# Esquematico_Luximetro.net
KiCad netlist of a schematic drawn in Altium Designer
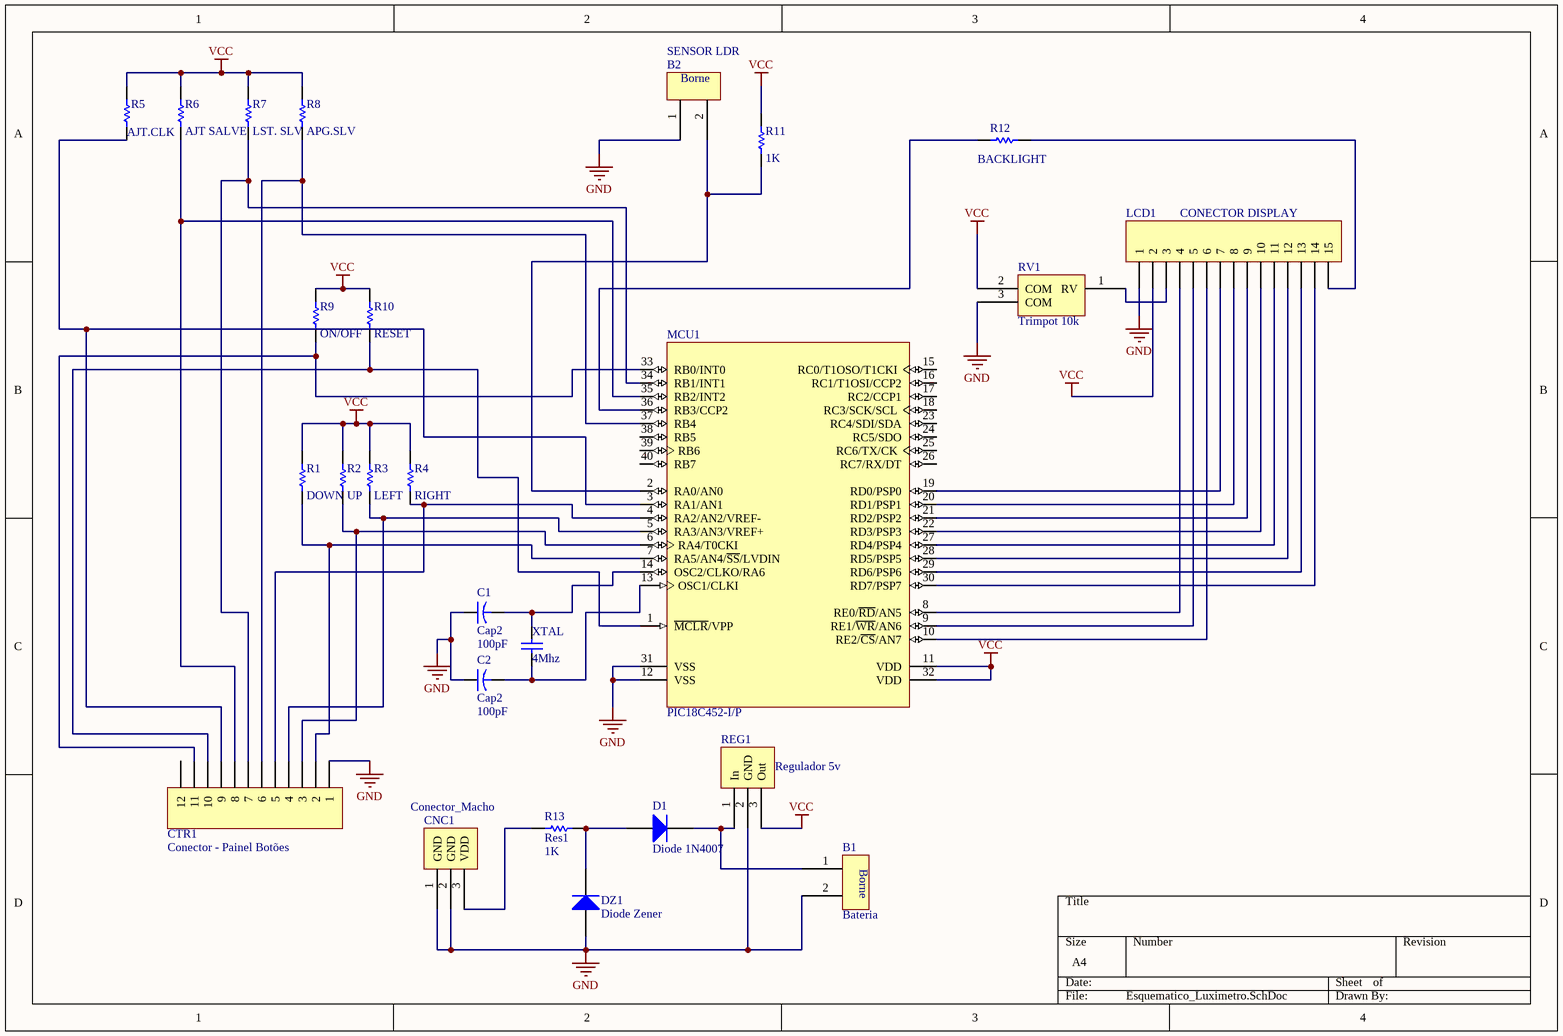
[diagram p0: Esquematico_Luximetro.SchDoc]

(export (version "E")
  (design (tool "Eeschema 10.0.6"))
  (components
    (comp (ref "B1") (value "Bateria") (footprint "PCB_BORNE") (libsource (lib "") (part "Borne_1")))
    (comp (ref "B2")
      (value "SENSOR LDR")
      (footprint "PCB_BORNE")
      (libsource (lib "Minha_Biblioteca") (part "Borne"))
    )
    (comp (ref "C1")
      (value "Cap2")
      (footprint "CAPR5-4X5")
      (description "Capacitor")
      (fields (field (name "ALTIUM_VALUE") "100pF") (field (name "PUBLISHER") "Altium Limited"))
      (libsource (lib "Miscellaneous Devices") (part "Cap2"))
    )
    (comp (ref "C2")
      (value "Cap2")
      (footprint "CAPR5-4X5")
      (description "Capacitor")
      (fields (field (name "ALTIUM_VALUE") "100pF") (field (name "PUBLISHER") "Altium Limited"))
      (libsource (lib "Miscellaneous Devices") (part "Cap2"))
    )
    (comp (ref "CNC1")
      (value "Conector_Macho")
      (footprint "PCB_Conector")
      (libsource (lib "Minha_Biblioteca") (part "Conector"))
    )
    (comp (ref "CTR1")
      (value "Conector - Painel Botões")
      (footprint "HDR1X12")
      (description "Header, 12-Pin")
      (fields (field (name "PUBLISHER") "Altium Limited"))
      (libsource (lib "Miscellaneous Connectors") (part "Header 12"))
    )
    (comp (ref "D1")
      (value "Diode 1N4007")
      (footprint "DO-41")
      (description "1 Amp General Purpose Rectifier")
      (fields (field (name "PUBLISHER") "Altium Limited"))
      (libsource (lib "Miscellaneous Devices") (part "Diode 1N4007"))
    )
    (comp (ref "DZ1")
      (value "Diode Zener")
      (footprint "DO-41")
      (description "1 Amp General Purpose Rectifier")
      (fields (field (name "PUBLISHER") "Altium Limited"))
      (libsource (lib "Miscellaneous Devices") (part "Diode 1N4007"))
    )
    (comp (ref "LCD1")
      (value "CONECTOR DISPLAY")
      (footprint "HDR1X15")
      (description "Header, 15-Pin")
      (fields (field (name "PUBLISHER") "Altium Limited"))
      (libsource (lib "Miscellaneous Connectors") (part "Header 15"))
    )
    (comp (ref "MCU1")
      (value "PIC18C452-I/P")
      (footprint "PDIP600-40")
      (fields (field (name "PUBLISHER") "Altium Limited"))
      (libsource (lib "Microchip Microcontroller 8-Bit PIC18") (part "PIC18C452-I/P"))
    )
    (comp (ref "R1")
      (value "DOWN")
      (footprint "AXIAL-0.3")
      (description "Resistor")
      (fields (field (name "Comment") "Res2") (field (name "PUBLISHER") "Altium Limited"))
      (libsource (lib "Miscellaneous Devices") (part "Res1"))
    )
    (comp (ref "R2")
      (value "UP")
      (footprint "AXIAL-0.3")
      (description "Resistor")
      (fields (field (name "Comment") "Res3") (field (name "PUBLISHER") "Altium Limited"))
      (libsource (lib "Miscellaneous Devices") (part "Res1"))
    )
    (comp (ref "R3")
      (value "LEFT")
      (footprint "AXIAL-0.3")
      (description "Resistor")
      (fields (field (name "Comment") "Res4") (field (name "PUBLISHER") "Altium Limited"))
      (libsource (lib "Miscellaneous Devices") (part "Res1"))
    )
    (comp (ref "R4")
      (value "RIGHT")
      (footprint "AXIAL-0.3")
      (description "Resistor")
      (fields (field (name "Comment") "Res5") (field (name "PUBLISHER") "Altium Limited"))
      (libsource (lib "Miscellaneous Devices") (part "Res1"))
    )
    (comp (ref "R5")
      (value "AJT.CLK")
      (footprint "AXIAL-0.3")
      (description "Resistor")
      (fields (field (name "Comment") "Res1") (field (name "PUBLISHER") "Altium Limited"))
      (libsource (lib "Miscellaneous Devices") (part "Res1"))
    )
    (comp (ref "R6")
      (value "AJT SALVE")
      (footprint "AXIAL-0.3")
      (description "Resistor")
      (fields (field (name "Comment") "Res1") (field (name "PUBLISHER") "Altium Limited"))
      (libsource (lib "Miscellaneous Devices") (part "Res1"))
    )
    (comp (ref "R7")
      (value "LST. SLV")
      (footprint "AXIAL-0.3")
      (description "Resistor")
      (fields (field (name "Comment") "Res1") (field (name "PUBLISHER") "Altium Limited"))
      (libsource (lib "Miscellaneous Devices") (part "Res1"))
    )
    (comp (ref "R8")
      (value "APG.SLV")
      (footprint "AXIAL-0.3")
      (description "Resistor")
      (fields (field (name "Comment") "Res1") (field (name "PUBLISHER") "Altium Limited"))
      (libsource (lib "Miscellaneous Devices") (part "Res1"))
    )
    (comp (ref "R9")
      (value "ON/OFF")
      (footprint "AXIAL-0.3")
      (description "Resistor")
      (fields (field (name "Comment") "Res1") (field (name "PUBLISHER") "Altium Limited"))
      (libsource (lib "Miscellaneous Devices") (part "Res1"))
    )
    (comp (ref "R10")
      (value "RESET")
      (footprint "AXIAL-0.3")
      (description "Resistor")
      (fields (field (name "Comment") "Res1") (field (name "PUBLISHER") "Altium Limited"))
      (libsource (lib "Miscellaneous Devices") (part "Res1"))
    )
    (comp (ref "R11")
      (value "1K")
      (footprint "AXIAL-0.3")
      (description "Resistor")
      (fields (field (name "Comment") "Res5") (field (name "PUBLISHER") "Altium Limited"))
      (libsource (lib "Miscellaneous Devices") (part "Res1"))
    )
    (comp (ref "R12")
      (value "BACKLIGHT")
      (footprint "AXIAL-0.3")
      (description "Resistor")
      (fields (field (name "PUBLISHER") "Altium Limited"))
      (libsource (lib "Miscellaneous Devices") (part "Res1"))
    )
    (comp (ref "R13")
      (value "Res1")
      (footprint "AXIAL-0.3")
      (description "Resistor")
      (fields (field (name "ALTIUM_VALUE") "1K") (field (name "PUBLISHER") "Altium Limited"))
      (libsource (lib "Miscellaneous Devices") (part "Res1"))
    )
    (comp (ref "REG1")
      (value "Regulador 5v")
      (footprint "PCB_CI7805")
      (libsource (lib "Minha_Biblioteca") (part "Regulador"))
    )
    (comp (ref "RV1")
      (value "Trimpot 10k")
      (footprint "PCB_TRIMPOT")
      (libsource (lib "Minha_Biblioteca") (part "Trimpot"))
    )
    (comp (ref "XTAL")
      (value "4Mhz")
      (footprint "RAD-0.3")
      (description "Capacitor")
      (fields (field (name "Comment") "Cap") (field (name "PUBLISHER") "Altium Limited"))
      (libsource (lib "Miscellaneous Devices") (part "Cap"))
    )
  )
  (nets
    (net (code "1") (name "GND") (class "Default")
      (node (ref "B1") (pin "2") (pintype "passive"))
      (node (ref "B2") (pin "1") (pintype "passive"))
      (node (ref "C1") (pin "1") (pinfunction "1_1") (pintype "passive"))
      (node (ref "C2") (pin "1") (pinfunction "1_1") (pintype "passive"))
      (node (ref "CNC1") (pin "1") (pinfunction "GND_1") (pintype "passive"))
      (node (ref "CNC1") (pin "2") (pinfunction "GND_2") (pintype "passive"))
      (node (ref "CTR1") (pin "1") (pinfunction "1_1") (pintype "passive"))
      (node (ref "DZ1") (pin "1") (pinfunction "A_1") (pintype "passive"))
      (node (ref "LCD1") (pin "1") (pinfunction "1_1") (pintype "passive"))
      (node (ref "MCU1") (pin "12") (pinfunction "VSS_12") (pintype "power_in"))
      (node (ref "MCU1") (pin "31") (pinfunction "VSS_31") (pintype "power_in"))
      (node (ref "REG1") (pin "2") (pinfunction "GND_2") (pintype "passive"))
      (node (ref "RV1") (pin "3") (pinfunction "COM_3") (pintype "passive"))
    )
    (net (code "2") (name "Net-(CNC1-VDD)") (class "Default")
      (node (ref "CNC1") (pin "3") (pinfunction "VDD_3") (pintype "passive"))
      (node (ref "R13") (pin "1") (pinfunction "1_1") (pintype "passive"))
    )
    (net (code "3") (name "Net-(D1-A)") (class "Default")
      (node (ref "D1") (pin "1") (pinfunction "A_1") (pintype "passive"))
      (node (ref "DZ1") (pin "2") (pinfunction "K_2") (pintype "passive"))
      (node (ref "R13") (pin "2") (pinfunction "2_2") (pintype "passive"))
    )
    (net (code "4") (name "Net-(D1-K)") (class "Default")
      (node (ref "B1") (pin "1") (pintype "passive"))
      (node (ref "D1") (pin "2") (pinfunction "K_2") (pintype "passive"))
      (node (ref "REG1") (pin "1") (pinfunction "In_1") (pintype "passive"))
    )
    (net (code "5") (name "Net-(LCD1-Pad15)") (class "Default")
      (node (ref "LCD1") (pin "15") (pinfunction "15_15") (pintype "passive"))
      (node (ref "R12") (pin "2") (pinfunction "2_2") (pintype "passive"))
    )
    (net (code "6") (name "Net-(MCU1-OSC1{slash}CLKI)") (class "Default")
      (node (ref "C2") (pin "2") (pinfunction "2_2") (pintype "passive"))
      (node (ref "MCU1") (pin "13") (pinfunction "OSC1/CLKI_13") (pintype "input"))
      (node (ref "XTAL") (pin "1") (pinfunction "1_1") (pintype "passive"))
    )
    (net (code "7") (name "Net-(MCU1-OSC2{slash}CLKO{slash}RA6)") (class "Default")
      (node (ref "C1") (pin "2") (pinfunction "2_2") (pintype "passive"))
      (node (ref "MCU1") (pin "14") (pinfunction "OSC2/CLKO/RA6_14") (pintype "bidirectional"))
      (node (ref "XTAL") (pin "2") (pinfunction "2_2") (pintype "passive"))
    )
    (net (code "8") (name "Net-(MCU1-RA0{slash}AN0)") (class "Default")
      (node (ref "B2") (pin "2") (pintype "passive"))
      (node (ref "MCU1") (pin "2") (pinfunction "RA0/AN0_2") (pintype "bidirectional"))
      (node (ref "R11") (pin "2") (pinfunction "2_2") (pintype "passive"))
    )
    (net (code "9") (name "Net-(MCU1-RA1{slash}AN1)") (class "Default")
      (node (ref "CTR1") (pin "9") (pinfunction "9_9") (pintype "passive"))
      (node (ref "MCU1") (pin "3") (pinfunction "RA1/AN1_3") (pintype "bidirectional"))
      (node (ref "R5") (pin "1") (pinfunction "1_1") (pintype "passive"))
    )
    (net (code "10") (name "Net-(MCU1-RA2{slash}AN2{slash}VREF-)") (class "Default")
      (node (ref "CTR1") (pin "5") (pinfunction "5_5") (pintype "passive"))
      (node (ref "MCU1") (pin "4") (pinfunction "RA2/AN2/VREF-_4") (pintype "bidirectional"))
      (node (ref "R4") (pin "2") (pinfunction "2_2") (pintype "passive"))
    )
    (net (code "11") (name "Net-(MCU1-RA3{slash}AN3{slash}VREF+)") (class "Default")
      (node (ref "CTR1") (pin "4") (pinfunction "4_4") (pintype "passive"))
      (node (ref "MCU1") (pin "5") (pinfunction "RA3/AN3/VREF+_5") (pintype "bidirectional"))
      (node (ref "R3") (pin "2") (pinfunction "2_2") (pintype "passive"))
    )
    (net (code "12") (name "Net-(MCU1-RA4{slash}T0CKI)") (class "Default")
      (node (ref "CTR1") (pin "3") (pinfunction "3_3") (pintype "passive"))
      (node (ref "MCU1") (pin "6") (pinfunction "RA4/T0CKI_6") (pintype "bidirectional"))
      (node (ref "R2") (pin "2") (pinfunction "2_2") (pintype "passive"))
    )
    (net (code "13") (name "Net-(MCU1-RA5{slash}AN4{slash}~{SS}{slash}LVDIN)") (class "Default")
      (node (ref "CTR1") (pin "2") (pinfunction "2_2") (pintype "passive"))
      (node (ref "MCU1") (pin "7") (pinfunction "RA5/AN4/~{SS}/LVDIN_7") (pintype "bidirectional"))
      (node (ref "R1") (pin "2") (pinfunction "2_2") (pintype "passive"))
    )
    (net (code "14") (name "Net-(MCU1-RB0{slash}INT0)") (class "Default")
      (node (ref "CTR1") (pin "11") (pinfunction "11_11") (pintype "passive"))
      (node (ref "MCU1") (pin "33") (pinfunction "RB0/INT0_33") (pintype "bidirectional"))
      (node (ref "R9") (pin "2") (pinfunction "2_2") (pintype "passive"))
    )
    (net (code "15") (name "Net-(MCU1-RB1{slash}INT1)") (class "Default")
      (node (ref "CTR1") (pin "7") (pinfunction "7_7") (pintype "passive"))
      (node (ref "MCU1") (pin "34") (pinfunction "RB1/INT1_34") (pintype "bidirectional"))
      (node (ref "R7") (pin "1") (pinfunction "1_1") (pintype "passive"))
    )
    (net (code "16") (name "Net-(MCU1-RB2{slash}INT2)") (class "Default")
      (node (ref "CTR1") (pin "8") (pinfunction "8_8") (pintype "passive"))
      (node (ref "MCU1") (pin "35") (pinfunction "RB2/INT2_35") (pintype "bidirectional"))
      (node (ref "R6") (pin "1") (pinfunction "1_1") (pintype "passive"))
    )
    (net (code "17") (name "Net-(MCU1-RB3{slash}CCP2)") (class "Default")
      (node (ref "MCU1") (pin "36") (pinfunction "RB3/CCP2_36") (pintype "bidirectional"))
      (node (ref "R12") (pin "1") (pinfunction "1_1") (pintype "passive"))
    )
    (net (code "18") (name "Net-(MCU1-RB4)") (class "Default")
      (node (ref "CTR1") (pin "6") (pinfunction "6_6") (pintype "passive"))
      (node (ref "MCU1") (pin "37") (pinfunction "RB4_37") (pintype "bidirectional"))
      (node (ref "R8") (pin "1") (pinfunction "1_1") (pintype "passive"))
    )
    (net (code "19") (name "Net-(MCU1-RD0{slash}PSP0)") (class "Default")
      (node (ref "LCD1") (pin "7") (pinfunction "7_7") (pintype "passive"))
      (node (ref "MCU1") (pin "19") (pinfunction "RD0/PSP0_19") (pintype "bidirectional"))
    )
    (net (code "20") (name "Net-(MCU1-RD1{slash}PSP1)") (class "Default")
      (node (ref "LCD1") (pin "8") (pinfunction "8_8") (pintype "passive"))
      (node (ref "MCU1") (pin "20") (pinfunction "RD1/PSP1_20") (pintype "bidirectional"))
    )
    (net (code "21") (name "Net-(MCU1-RD2{slash}PSP2)") (class "Default")
      (node (ref "LCD1") (pin "9") (pinfunction "9_9") (pintype "passive"))
      (node (ref "MCU1") (pin "21") (pinfunction "RD2/PSP2_21") (pintype "bidirectional"))
    )
    (net (code "22") (name "Net-(MCU1-RD3{slash}PSP3)") (class "Default")
      (node (ref "LCD1") (pin "10") (pinfunction "10_10") (pintype "passive"))
      (node (ref "MCU1") (pin "22") (pinfunction "RD3/PSP3_22") (pintype "bidirectional"))
    )
    (net (code "23") (name "Net-(MCU1-RD4{slash}PSP4)") (class "Default")
      (node (ref "LCD1") (pin "11") (pinfunction "11_11") (pintype "passive"))
      (node (ref "MCU1") (pin "27") (pinfunction "RD4/PSP4_27") (pintype "bidirectional"))
    )
    (net (code "24") (name "Net-(MCU1-RD5{slash}PSP5)") (class "Default")
      (node (ref "LCD1") (pin "12") (pinfunction "12_12") (pintype "passive"))
      (node (ref "MCU1") (pin "28") (pinfunction "RD5/PSP5_28") (pintype "bidirectional"))
    )
    (net (code "25") (name "Net-(MCU1-RD6{slash}PSP6)") (class "Default")
      (node (ref "LCD1") (pin "13") (pinfunction "13_13") (pintype "passive"))
      (node (ref "MCU1") (pin "29") (pinfunction "RD6/PSP6_29") (pintype "bidirectional"))
    )
    (net (code "26") (name "Net-(MCU1-RD7{slash}PSP7)") (class "Default")
      (node (ref "LCD1") (pin "14") (pinfunction "14_14") (pintype "passive"))
      (node (ref "MCU1") (pin "30") (pinfunction "RD7/PSP7_30") (pintype "bidirectional"))
    )
    (net (code "27") (name "Net-(MCU1-RE0{slash}~{RD}{slash}AN5)") (class "Default")
      (node (ref "LCD1") (pin "4") (pinfunction "4_4") (pintype "passive"))
      (node (ref "MCU1") (pin "8") (pinfunction "RE0/~{RD}/AN5_8") (pintype "bidirectional"))
    )
    (net (code "28") (name "Net-(MCU1-RE1{slash}~{WR}{slash}AN6)") (class "Default")
      (node (ref "LCD1") (pin "5") (pinfunction "5_5") (pintype "passive"))
      (node (ref "MCU1") (pin "9") (pinfunction "RE1/~{WR}/AN6_9") (pintype "bidirectional"))
    )
    (net (code "29") (name "Net-(MCU1-RE2{slash}~{CS}{slash}AN7)") (class "Default")
      (node (ref "LCD1") (pin "6") (pinfunction "6_6") (pintype "passive"))
      (node (ref "MCU1") (pin "10") (pinfunction "RE2/~{CS}/AN7_10") (pintype "bidirectional"))
    )
    (net (code "30") (name "Net-(MCU1-~{MCLR}{slash}VPP)") (class "Default")
      (node (ref "CTR1") (pin "10") (pinfunction "10_10") (pintype "passive"))
      (node (ref "MCU1") (pin "1") (pinfunction "~{MCLR}/VPP_1") (pintype "input"))
      (node (ref "R10") (pin "2") (pinfunction "2_2") (pintype "passive"))
    )
    (net (code "31") (name "Net-(RV1-RV)") (class "Default")
      (node (ref "LCD1") (pin "3") (pinfunction "3_3") (pintype "passive"))
      (node (ref "RV1") (pin "1") (pinfunction "RV_1") (pintype "passive"))
    )
    (net (code "32") (name "VCC") (class "Default")
      (node (ref "LCD1") (pin "2") (pinfunction "2_2") (pintype "passive"))
      (node (ref "MCU1") (pin "11") (pinfunction "VDD_11") (pintype "power_in"))
      (node (ref "MCU1") (pin "32") (pinfunction "VDD_32") (pintype "power_in"))
      (node (ref "R1") (pin "1") (pinfunction "1_1") (pintype "passive"))
      (node (ref "R10") (pin "1") (pinfunction "1_1") (pintype "passive"))
      (node (ref "R11") (pin "1") (pinfunction "1_1") (pintype "passive"))
      (node (ref "R2") (pin "1") (pinfunction "1_1") (pintype "passive"))
      (node (ref "R3") (pin "1") (pinfunction "1_1") (pintype "passive"))
      (node (ref "R4") (pin "1") (pinfunction "1_1") (pintype "passive"))
      (node (ref "R5") (pin "2") (pinfunction "2_2") (pintype "passive"))
      (node (ref "R6") (pin "2") (pinfunction "2_2") (pintype "passive"))
      (node (ref "R7") (pin "2") (pinfunction "2_2") (pintype "passive"))
      (node (ref "R8") (pin "2") (pinfunction "2_2") (pintype "passive"))
      (node (ref "R9") (pin "1") (pinfunction "1_1") (pintype "passive"))
      (node (ref "REG1") (pin "3") (pinfunction "Out_3") (pintype "passive"))
      (node (ref "RV1") (pin "2") (pinfunction "COM_2") (pintype "passive"))
    )
    (net (code "33") (name "unconnected-(CTR1-Pad12)") (class "Default")
      (node (ref "CTR1") (pin "12") (pinfunction "12_12") (pintype "passive"))
    )
    (net (code "34") (name "unconnected-(MCU1-RB5-Pad38)") (class "Default")
      (node (ref "MCU1") (pin "38") (pinfunction "RB5_38") (pintype "bidirectional"))
    )
    (net (code "35") (name "unconnected-(MCU1-RB6-Pad39)") (class "Default")
      (node (ref "MCU1") (pin "39") (pinfunction "RB6_39") (pintype "bidirectional"))
    )
    (net (code "36") (name "unconnected-(MCU1-RB7-Pad40)") (class "Default")
      (node (ref "MCU1") (pin "40") (pinfunction "RB7_40") (pintype "bidirectional"))
    )
    (net (code "37") (name "unconnected-(MCU1-RC0{slash}T1OSO{slash}T1CKI-Pad15)") (class "Default")
      (node (ref "MCU1") (pin "15") (pinfunction "RC0/T1OSO/T1CKI_15") (pintype "bidirectional"))
    )
    (net (code "38") (name "unconnected-(MCU1-RC1{slash}T1OSI{slash}CCP2-Pad16)") (class "Default")
      (node (ref "MCU1") (pin "16") (pinfunction "RC1/T1OSI/CCP2_16") (pintype "bidirectional"))
    )
    (net (code "39") (name "unconnected-(MCU1-RC2{slash}CCP1-Pad17)") (class "Default")
      (node (ref "MCU1") (pin "17") (pinfunction "RC2/CCP1_17") (pintype "bidirectional"))
    )
    (net (code "40") (name "unconnected-(MCU1-RC3{slash}SCK{slash}SCL-Pad18)") (class "Default")
      (node (ref "MCU1") (pin "18") (pinfunction "RC3/SCK/SCL_18") (pintype "bidirectional"))
    )
    (net (code "41") (name "unconnected-(MCU1-RC4{slash}SDI{slash}SDA-Pad23)") (class "Default")
      (node (ref "MCU1") (pin "23") (pinfunction "RC4/SDI/SDA_23") (pintype "bidirectional"))
    )
    (net (code "42") (name "unconnected-(MCU1-RC5{slash}SDO-Pad24)") (class "Default")
      (node (ref "MCU1") (pin "24") (pinfunction "RC5/SDO_24") (pintype "bidirectional"))
    )
    (net (code "43") (name "unconnected-(MCU1-RC6{slash}TX{slash}CK-Pad25)") (class "Default")
      (node (ref "MCU1") (pin "25") (pinfunction "RC6/TX/CK_25") (pintype "bidirectional"))
    )
    (net (code "44") (name "unconnected-(MCU1-RC7{slash}RX{slash}DT-Pad26)") (class "Default")
      (node (ref "MCU1") (pin "26") (pinfunction "RC7/RX/DT_26") (pintype "bidirectional"))
    )
  )
)
